# CPU3.net
KiCad netlist of a schematic drawn in Altium Designer
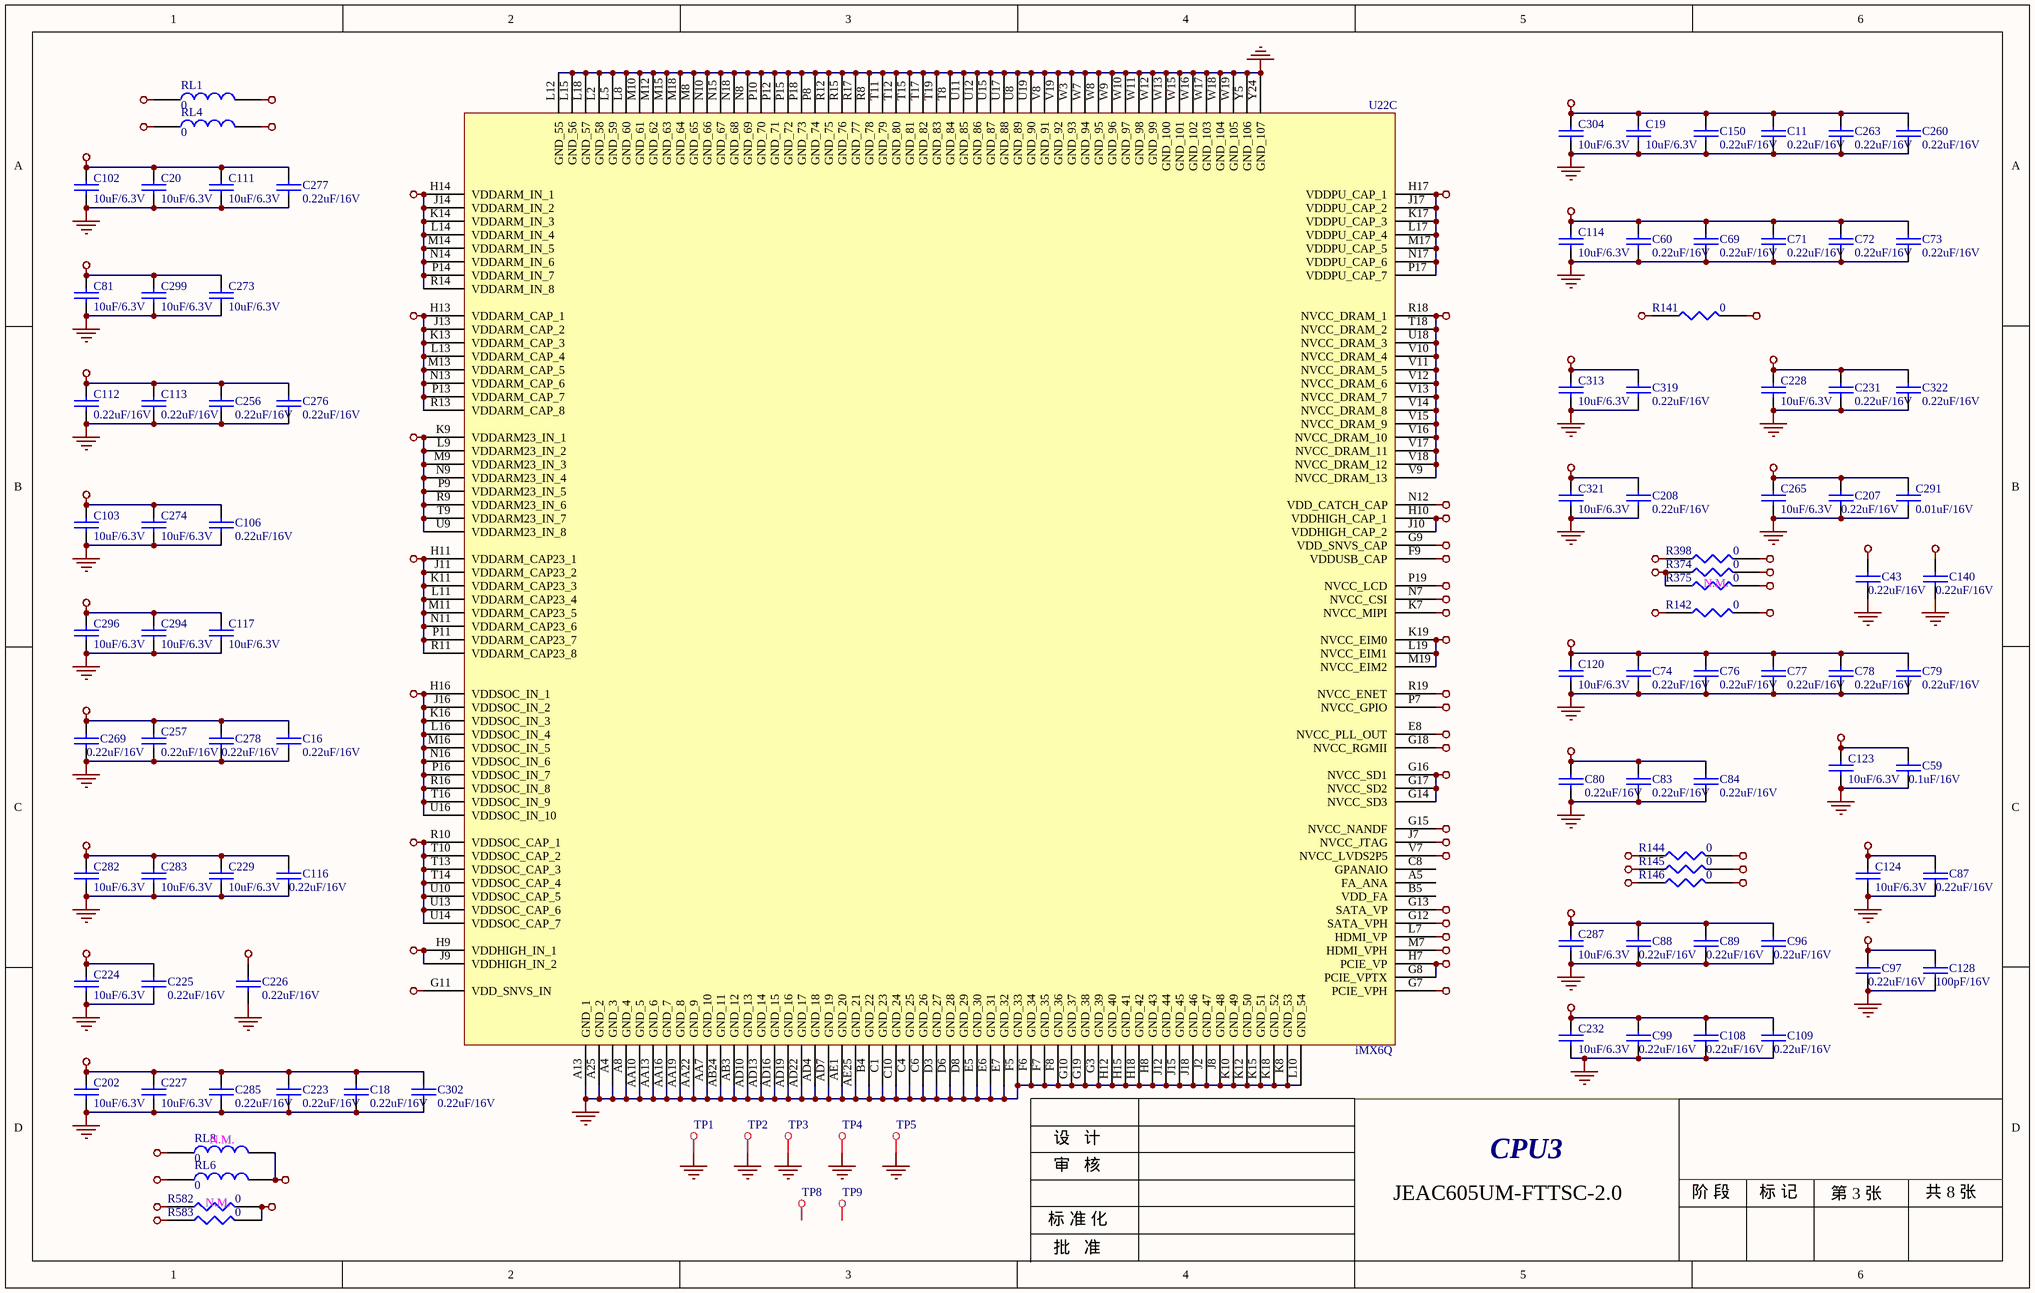
[diagram p0: CPU3.schdoc]

(export (version "E")
  (design (tool "Eeschema 10.0.6"))
  (components
    (comp (ref "C11")
      (value "0.22uF/16V")
      (footprint "C0402")
      (description "Capacitor")
      (libsource (lib "*") (part "CAP"))
    )
    (comp (ref "C16")
      (value "0.22uF/16V")
      (footprint "C0402")
      (description "Capacitor")
      (libsource (lib "*") (part "CAP"))
    )
    (comp (ref "C18")
      (value "0.22uF/16V")
      (footprint "C0402")
      (description "Capacitor")
      (libsource (lib "*") (part "CAP"))
    )
    (comp (ref "C19")
      (value "10uF/6.3V")
      (footprint "C0603")
      (description "Capacitor")
      (libsource (lib "*") (part "CAP"))
    )
    (comp (ref "C20")
      (value "10uF/6.3V")
      (footprint "C0603")
      (description "Capacitor")
      (libsource (lib "*") (part "CAP"))
    )
    (comp (ref "C43")
      (value "0.22uF/16V")
      (footprint "C0402")
      (description "Capacitor")
      (libsource (lib "*") (part "CAP"))
    )
    (comp (ref "C59")
      (value "0.1uF/16V")
      (footprint "C0402")
      (description "Capacitor")
      (libsource (lib "*") (part "CAP"))
    )
    (comp (ref "C60")
      (value "0.22uF/16V")
      (footprint "C0402")
      (description "Capacitor")
      (libsource (lib "*") (part "CAP"))
    )
    (comp (ref "C69")
      (value "0.22uF/16V")
      (footprint "C0402")
      (description "Capacitor")
      (libsource (lib "*") (part "CAP"))
    )
    (comp (ref "C71")
      (value "0.22uF/16V")
      (footprint "C0402")
      (description "Capacitor")
      (libsource (lib "*") (part "CAP"))
    )
    (comp (ref "C72")
      (value "0.22uF/16V")
      (footprint "C0402")
      (description "Capacitor")
      (libsource (lib "*") (part "CAP"))
    )
    (comp (ref "C73")
      (value "0.22uF/16V")
      (footprint "C0402")
      (description "Capacitor")
      (libsource (lib "*") (part "CAP"))
    )
    (comp (ref "C74")
      (value "0.22uF/16V")
      (footprint "C0402")
      (description "Capacitor")
      (libsource (lib "*") (part "CAP"))
    )
    (comp (ref "C76")
      (value "0.22uF/16V")
      (footprint "C0402")
      (description "Capacitor")
      (libsource (lib "*") (part "CAP"))
    )
    (comp (ref "C77")
      (value "0.22uF/16V")
      (footprint "C0402")
      (description "Capacitor")
      (libsource (lib "*") (part "CAP"))
    )
    (comp (ref "C78")
      (value "0.22uF/16V")
      (footprint "C0402")
      (description "Capacitor")
      (libsource (lib "*") (part "CAP"))
    )
    (comp (ref "C79")
      (value "0.22uF/16V")
      (footprint "C0402")
      (description "Capacitor")
      (libsource (lib "*") (part "CAP"))
    )
    (comp (ref "C80")
      (value "0.22uF/16V")
      (footprint "C0402")
      (description "Capacitor")
      (libsource (lib "*") (part "CAP"))
    )
    (comp (ref "C81")
      (value "10uF/6.3V")
      (footprint "C0603")
      (description "Capacitor")
      (libsource (lib "*") (part "CAP"))
    )
    (comp (ref "C83")
      (value "0.22uF/16V")
      (footprint "C0402")
      (description "Capacitor")
      (libsource (lib "*") (part "CAP"))
    )
    (comp (ref "C84")
      (value "0.22uF/16V")
      (footprint "C0402")
      (description "Capacitor")
      (libsource (lib "*") (part "CAP"))
    )
    (comp (ref "C87")
      (value "0.22uF/16V")
      (footprint "C0402")
      (description "Capacitor")
      (libsource (lib "*") (part "CAP"))
    )
    (comp (ref "C88")
      (value "0.22uF/16V")
      (footprint "C0402")
      (description "Capacitor")
      (libsource (lib "*") (part "CAP"))
    )
    (comp (ref "C89")
      (value "0.22uF/16V")
      (footprint "C0402")
      (description "Capacitor")
      (libsource (lib "*") (part "CAP"))
    )
    (comp (ref "C96")
      (value "0.22uF/16V")
      (footprint "C0402")
      (description "Capacitor")
      (libsource (lib "*") (part "CAP"))
    )
    (comp (ref "C97")
      (value "0.22uF/16V")
      (footprint "C0402")
      (description "Capacitor")
      (libsource (lib "*") (part "CAP"))
    )
    (comp (ref "C99")
      (value "0.22uF/16V")
      (footprint "C0402")
      (description "Capacitor")
      (libsource (lib "*") (part "CAP"))
    )
    (comp (ref "C102")
      (value "10uF/6.3V")
      (footprint "C0603")
      (description "Capacitor")
      (libsource (lib "*") (part "CAP"))
    )
    (comp (ref "C103")
      (value "10uF/6.3V")
      (footprint "C0603")
      (description "Capacitor")
      (libsource (lib "*") (part "CAP"))
    )
    (comp (ref "C106")
      (value "0.22uF/16V")
      (footprint "C0402")
      (description "Capacitor")
      (libsource (lib "*") (part "CAP"))
    )
    (comp (ref "C108")
      (value "0.22uF/16V")
      (footprint "C0402")
      (description "Capacitor")
      (libsource (lib "*") (part "CAP"))
    )
    (comp (ref "C109")
      (value "0.22uF/16V")
      (footprint "C0402")
      (description "Capacitor")
      (libsource (lib "*") (part "CAP"))
    )
    (comp (ref "C111")
      (value "10uF/6.3V")
      (footprint "C0603")
      (description "Capacitor")
      (libsource (lib "*") (part "CAP"))
    )
    (comp (ref "C112")
      (value "0.22uF/16V")
      (footprint "C0402")
      (description "Capacitor")
      (libsource (lib "*") (part "CAP"))
    )
    (comp (ref "C113")
      (value "0.22uF/16V")
      (footprint "C0402")
      (description "Capacitor")
      (libsource (lib "*") (part "CAP"))
    )
    (comp (ref "C114")
      (value "10uF/6.3V")
      (footprint "C0603")
      (description "Capacitor")
      (libsource (lib "*") (part "CAP"))
    )
    (comp (ref "C116")
      (value "0.22uF/16V")
      (footprint "C0402")
      (description "Capacitor")
      (libsource (lib "*") (part "CAP"))
    )
    (comp (ref "C117")
      (value "10uF/6.3V")
      (footprint "C0603")
      (description "Capacitor")
      (libsource (lib "*") (part "CAP"))
    )
    (comp (ref "C120")
      (value "10uF/6.3V")
      (footprint "C0603")
      (description "Capacitor")
      (libsource (lib "*") (part "CAP"))
    )
    (comp (ref "C123")
      (value "10uF/6.3V")
      (footprint "C0603")
      (description "Capacitor")
      (libsource (lib "*") (part "CAP"))
    )
    (comp (ref "C124")
      (value "10uF/6.3V")
      (footprint "C0603")
      (description "Capacitor")
      (libsource (lib "*") (part "CAP"))
    )
    (comp (ref "C128")
      (value "100pF/16V")
      (footprint "C0402")
      (description "Capacitor")
      (libsource (lib "*") (part "CAP"))
    )
    (comp (ref "C140")
      (value "0.22uF/16V")
      (footprint "C0402")
      (description "Capacitor")
      (libsource (lib "*") (part "CAP"))
    )
    (comp (ref "C150")
      (value "0.22uF/16V")
      (footprint "C0402")
      (description "Capacitor")
      (libsource (lib "*") (part "CAP"))
    )
    (comp (ref "C202")
      (value "10uF/6.3V")
      (footprint "C0603")
      (description "Capacitor")
      (libsource (lib "*") (part "CAP"))
    )
    (comp (ref "C207")
      (value "0.22uF/16V")
      (footprint "C0402")
      (description "Capacitor")
      (libsource (lib "*") (part "CAP"))
    )
    (comp (ref "C208")
      (value "0.22uF/16V")
      (footprint "C0402")
      (description "Capacitor")
      (libsource (lib "*") (part "CAP"))
    )
    (comp (ref "C223")
      (value "0.22uF/16V")
      (footprint "C0402")
      (description "Capacitor")
      (libsource (lib "*") (part "CAP"))
    )
    (comp (ref "C224")
      (value "10uF/6.3V")
      (footprint "C0603")
      (description "Capacitor")
      (libsource (lib "*") (part "CAP"))
    )
    (comp (ref "C225")
      (value "0.22uF/16V")
      (footprint "C0402")
      (description "Capacitor")
      (libsource (lib "*") (part "CAP"))
    )
    (comp (ref "C226")
      (value "0.22uF/16V")
      (footprint "C0402")
      (description "Capacitor")
      (libsource (lib "*") (part "CAP"))
    )
    (comp (ref "C227")
      (value "10uF/6.3V")
      (footprint "C0603")
      (description "Capacitor")
      (libsource (lib "*") (part "CAP"))
    )
    (comp (ref "C228")
      (value "10uF/6.3V")
      (footprint "C0603")
      (description "Capacitor")
      (libsource (lib "*") (part "CAP"))
    )
    (comp (ref "C229")
      (value "10uF/6.3V")
      (footprint "C0603")
      (description "Capacitor")
      (libsource (lib "*") (part "CAP"))
    )
    (comp (ref "C231")
      (value "0.22uF/16V")
      (footprint "C0402")
      (description "Capacitor")
      (libsource (lib "*") (part "CAP"))
    )
    (comp (ref "C232")
      (value "10uF/6.3V")
      (footprint "C0603")
      (description "Capacitor")
      (libsource (lib "*") (part "CAP"))
    )
    (comp (ref "C256")
      (value "0.22uF/16V")
      (footprint "C0402")
      (description "Capacitor")
      (libsource (lib "*") (part "CAP"))
    )
    (comp (ref "C257")
      (value "0.22uF/16V")
      (footprint "C0402")
      (description "Capacitor")
      (libsource (lib "*") (part "CAP"))
    )
    (comp (ref "C260")
      (value "0.22uF/16V")
      (footprint "C0402")
      (description "Capacitor")
      (libsource (lib "*") (part "CAP"))
    )
    (comp (ref "C263")
      (value "0.22uF/16V")
      (footprint "C0402")
      (description "Capacitor")
      (libsource (lib "*") (part "CAP"))
    )
    (comp (ref "C265")
      (value "10uF/6.3V")
      (footprint "C0603")
      (description "Capacitor")
      (libsource (lib "*") (part "CAP"))
    )
    (comp (ref "C269")
      (value "0.22uF/16V")
      (footprint "C0402")
      (description "Capacitor")
      (libsource (lib "*") (part "CAP"))
    )
    (comp (ref "C273")
      (value "10uF/6.3V")
      (footprint "C0603")
      (description "Capacitor")
      (libsource (lib "*") (part "CAP"))
    )
    (comp (ref "C274")
      (value "10uF/6.3V")
      (footprint "C0603")
      (description "Capacitor")
      (libsource (lib "*") (part "CAP"))
    )
    (comp (ref "C276")
      (value "0.22uF/16V")
      (footprint "C0402")
      (description "Capacitor")
      (libsource (lib "*") (part "CAP"))
    )
    (comp (ref "C277")
      (value "0.22uF/16V")
      (footprint "C0402")
      (description "Capacitor")
      (libsource (lib "*") (part "CAP"))
    )
    (comp (ref "C278")
      (value "0.22uF/16V")
      (footprint "C0402")
      (description "Capacitor")
      (libsource (lib "*") (part "CAP"))
    )
    (comp (ref "C282")
      (value "10uF/6.3V")
      (footprint "C0603")
      (description "Capacitor")
      (libsource (lib "*") (part "CAP"))
    )
    (comp (ref "C283")
      (value "10uF/6.3V")
      (footprint "C0603")
      (description "Capacitor")
      (libsource (lib "*") (part "CAP"))
    )
    (comp (ref "C285")
      (value "0.22uF/16V")
      (footprint "C0402")
      (description "Capacitor")
      (libsource (lib "*") (part "CAP"))
    )
    (comp (ref "C287")
      (value "10uF/6.3V")
      (footprint "C0603")
      (description "Capacitor")
      (libsource (lib "*") (part "CAP"))
    )
    (comp (ref "C291")
      (value "0.01uF/16V")
      (footprint "C0402")
      (description "Capacitor")
      (libsource (lib "*") (part "CAP"))
    )
    (comp (ref "C294")
      (value "10uF/6.3V")
      (footprint "C0603")
      (description "Capacitor")
      (libsource (lib "*") (part "CAP"))
    )
    (comp (ref "C296")
      (value "10uF/6.3V")
      (footprint "C0603")
      (description "Capacitor")
      (libsource (lib "*") (part "CAP"))
    )
    (comp (ref "C299")
      (value "10uF/6.3V")
      (footprint "C0603")
      (description "Capacitor")
      (libsource (lib "*") (part "CAP"))
    )
    (comp (ref "C302")
      (value "0.22uF/16V")
      (footprint "C0402")
      (description "Capacitor")
      (libsource (lib "*") (part "CAP"))
    )
    (comp (ref "C304")
      (value "10uF/6.3V")
      (footprint "C0603")
      (description "Capacitor")
      (libsource (lib "*") (part "CAP"))
    )
    (comp (ref "C313")
      (value "10uF/6.3V")
      (footprint "C0603")
      (description "Capacitor")
      (libsource (lib "*") (part "CAP"))
    )
    (comp (ref "C319")
      (value "0.22uF/16V")
      (footprint "C0402")
      (description "Capacitor")
      (libsource (lib "*") (part "CAP"))
    )
    (comp (ref "C321")
      (value "10uF/6.3V")
      (footprint "C0603")
      (description "Capacitor")
      (libsource (lib "*") (part "CAP"))
    )
    (comp (ref "C322")
      (value "0.22uF/16V")
      (footprint "C0402")
      (description "Capacitor")
      (libsource (lib "*") (part "CAP"))
    )
    (comp (ref "R141") (value "0") (footprint "R0402") (libsource (lib "*") (part "RES1")))
    (comp (ref "R142") (value "0") (footprint "R0402") (libsource (lib "*") (part "RES1")))
    (comp (ref "R144") (value "0") (footprint "R0402") (libsource (lib "*") (part "RES1")))
    (comp (ref "R145") (value "0") (footprint "R0402") (libsource (lib "*") (part "RES1")))
    (comp (ref "R146") (value "0") (footprint "R0402") (libsource (lib "*") (part "RES1")))
    (comp (ref "R374") (value "0") (footprint "R0402") (libsource (lib "*") (part "RES1")))
    (comp (ref "R375") (value "0") (footprint "R0402") (libsource (lib "*") (part "RES1")))
    (comp (ref "R398") (value "0") (footprint "R0402") (libsource (lib "*") (part "RES1")))
    (comp (ref "R582") (value "0") (footprint "R0402") (libsource (lib "*") (part "RES1")))
    (comp (ref "R583") (value "0") (footprint "R0402") (libsource (lib "*") (part "RES1")))
    (comp (ref "RL1") (value "0") (footprint "L0805") (libsource (lib "*") (part "INDUCTOR")))
    (comp (ref "RL4") (value "0") (footprint "L0603") (libsource (lib "*") (part "INDUCTOR")))
    (comp (ref "RL6") (value "0") (footprint "L0603") (libsource (lib "*") (part "INDUCTOR")))
    (comp (ref "RL8") (value "0") (footprint "L0603") (libsource (lib "*") (part "INDUCTOR")))
    (comp (ref "TP1")
      (value "Testpoint")
      (footprint "PC3_5D2_0")
      (libsource (lib "DXP-SCHLIB") (part "Testpoint"))
    )
    (comp (ref "TP2")
      (value "Testpoint")
      (footprint "PC3_5D2_0")
      (libsource (lib "DXP-SCHLIB") (part "Testpoint"))
    )
    (comp (ref "TP3")
      (value "Testpoint")
      (footprint "PC3_5D2_0")
      (libsource (lib "DXP-SCHLIB") (part "Testpoint"))
    )
    (comp (ref "TP4")
      (value "Testpoint")
      (footprint "PC3_5D2_0")
      (libsource (lib "DXP-SCHLIB") (part "Testpoint"))
    )
    (comp (ref "TP5")
      (value "Testpoint")
      (footprint "PC3_5D2_0")
      (libsource (lib "DXP-SCHLIB") (part "Testpoint"))
    )
    (comp (ref "TP8")
      (value "Testpoint")
      (footprint "MTH059_06")
      (libsource (lib "DXP-SCHLIB") (part "Testpoint"))
    )
    (comp (ref "TP9")
      (value "Testpoint")
      (footprint "MTH059_06")
      (libsource (lib "DXP-SCHLIB") (part "Testpoint"))
    )
    (comp (ref "U22") (value "iMX6Q") (footprint "U-BGA-624-0_8") (libsource (lib "Schlib1") (part "IMX6Q")))
  )
  (nets
    (net (code "1") (name "GND") (class "Default")
      (node (ref "C102") (pin "2") (pinfunction "2_2") (pintype "passive"))
      (node (ref "C103") (pin "2") (pinfunction "2_2") (pintype "passive"))
      (node (ref "C106") (pin "2") (pinfunction "2_2") (pintype "passive"))
      (node (ref "C108") (pin "2") (pinfunction "2_2") (pintype "passive"))
      (node (ref "C109") (pin "2") (pinfunction "2_2") (pintype "passive"))
      (node (ref "C11") (pin "2") (pinfunction "2_2") (pintype "passive"))
      (node (ref "C111") (pin "2") (pinfunction "2_2") (pintype "passive"))
      (node (ref "C112") (pin "2") (pinfunction "2_2") (pintype "passive"))
      (node (ref "C113") (pin "2") (pinfunction "2_2") (pintype "passive"))
      (node (ref "C114") (pin "2") (pinfunction "2_2") (pintype "passive"))
      (node (ref "C116") (pin "2") (pinfunction "2_2") (pintype "passive"))
      (node (ref "C117") (pin "2") (pinfunction "2_2") (pintype "passive"))
      (node (ref "C120") (pin "2") (pinfunction "2_2") (pintype "passive"))
      (node (ref "C123") (pin "2") (pinfunction "2_2") (pintype "passive"))
      (node (ref "C124") (pin "2") (pinfunction "2_2") (pintype "passive"))
      (node (ref "C128") (pin "2") (pinfunction "2_2") (pintype "passive"))
      (node (ref "C140") (pin "2") (pinfunction "2_2") (pintype "passive"))
      (node (ref "C150") (pin "2") (pinfunction "2_2") (pintype "passive"))
      (node (ref "C16") (pin "2") (pinfunction "2_2") (pintype "passive"))
      (node (ref "C18") (pin "2") (pinfunction "2_2") (pintype "passive"))
      (node (ref "C19") (pin "2") (pinfunction "2_2") (pintype "passive"))
      (node (ref "C20") (pin "2") (pinfunction "2_2") (pintype "passive"))
      (node (ref "C202") (pin "2") (pinfunction "2_2") (pintype "passive"))
      (node (ref "C207") (pin "2") (pinfunction "2_2") (pintype "passive"))
      (node (ref "C208") (pin "2") (pinfunction "2_2") (pintype "passive"))
      (node (ref "C223") (pin "2") (pinfunction "2_2") (pintype "passive"))
      (node (ref "C224") (pin "2") (pinfunction "2_2") (pintype "passive"))
      (node (ref "C225") (pin "2") (pinfunction "2_2") (pintype "passive"))
      (node (ref "C226") (pin "2") (pinfunction "2_2") (pintype "passive"))
      (node (ref "C227") (pin "2") (pinfunction "2_2") (pintype "passive"))
      (node (ref "C228") (pin "2") (pinfunction "2_2") (pintype "passive"))
      (node (ref "C229") (pin "2") (pinfunction "2_2") (pintype "passive"))
      (node (ref "C231") (pin "2") (pinfunction "2_2") (pintype "passive"))
      (node (ref "C232") (pin "2") (pinfunction "2_2") (pintype "passive"))
      (node (ref "C256") (pin "2") (pinfunction "2_2") (pintype "passive"))
      (node (ref "C257") (pin "2") (pinfunction "2_2") (pintype "passive"))
      (node (ref "C260") (pin "2") (pinfunction "2_2") (pintype "passive"))
      (node (ref "C263") (pin "2") (pinfunction "2_2") (pintype "passive"))
      (node (ref "C265") (pin "2") (pinfunction "2_2") (pintype "passive"))
      (node (ref "C269") (pin "2") (pinfunction "2_2") (pintype "passive"))
      (node (ref "C273") (pin "2") (pinfunction "2_2") (pintype "passive"))
      (node (ref "C274") (pin "2") (pinfunction "2_2") (pintype "passive"))
      (node (ref "C276") (pin "2") (pinfunction "2_2") (pintype "passive"))
      (node (ref "C277") (pin "2") (pinfunction "2_2") (pintype "passive"))
      (node (ref "C278") (pin "2") (pinfunction "2_2") (pintype "passive"))
      (node (ref "C282") (pin "2") (pinfunction "2_2") (pintype "passive"))
      (node (ref "C283") (pin "2") (pinfunction "2_2") (pintype "passive"))
      (node (ref "C285") (pin "2") (pinfunction "2_2") (pintype "passive"))
      (node (ref "C287") (pin "2") (pinfunction "2_2") (pintype "passive"))
      (node (ref "C291") (pin "2") (pinfunction "2_2") (pintype "passive"))
      (node (ref "C294") (pin "2") (pinfunction "2_2") (pintype "passive"))
      (node (ref "C296") (pin "2") (pinfunction "2_2") (pintype "passive"))
      (node (ref "C299") (pin "2") (pinfunction "2_2") (pintype "passive"))
      (node (ref "C302") (pin "2") (pinfunction "2_2") (pintype "passive"))
      (node (ref "C304") (pin "2") (pinfunction "2_2") (pintype "passive"))
      (node (ref "C313") (pin "2") (pinfunction "2_2") (pintype "passive"))
      (node (ref "C319") (pin "2") (pinfunction "2_2") (pintype "passive"))
      (node (ref "C321") (pin "2") (pinfunction "2_2") (pintype "passive"))
      (node (ref "C322") (pin "2") (pinfunction "2_2") (pintype "passive"))
      (node (ref "C43") (pin "2") (pinfunction "2_2") (pintype "passive"))
      (node (ref "C59") (pin "2") (pinfunction "2_2") (pintype "passive"))
      (node (ref "C60") (pin "2") (pinfunction "2_2") (pintype "passive"))
      (node (ref "C69") (pin "2") (pinfunction "2_2") (pintype "passive"))
      (node (ref "C71") (pin "2") (pinfunction "2_2") (pintype "passive"))
      (node (ref "C72") (pin "2") (pinfunction "2_2") (pintype "passive"))
      (node (ref "C73") (pin "2") (pinfunction "2_2") (pintype "passive"))
      (node (ref "C74") (pin "2") (pinfunction "2_2") (pintype "passive"))
      (node (ref "C76") (pin "2") (pinfunction "2_2") (pintype "passive"))
      (node (ref "C77") (pin "2") (pinfunction "2_2") (pintype "passive"))
      (node (ref "C78") (pin "2") (pinfunction "2_2") (pintype "passive"))
      (node (ref "C79") (pin "2") (pinfunction "2_2") (pintype "passive"))
      (node (ref "C80") (pin "2") (pinfunction "2_2") (pintype "passive"))
      (node (ref "C81") (pin "2") (pinfunction "2_2") (pintype "passive"))
      (node (ref "C83") (pin "2") (pinfunction "2_2") (pintype "passive"))
      (node (ref "C84") (pin "2") (pinfunction "2_2") (pintype "passive"))
      (node (ref "C87") (pin "2") (pinfunction "2_2") (pintype "passive"))
      (node (ref "C88") (pin "2") (pinfunction "2_2") (pintype "passive"))
      (node (ref "C89") (pin "2") (pinfunction "2_2") (pintype "passive"))
      (node (ref "C96") (pin "2") (pinfunction "2_2") (pintype "passive"))
      (node (ref "C97") (pin "2") (pinfunction "2_2") (pintype "passive"))
      (node (ref "C99") (pin "2") (pinfunction "2_2") (pintype "passive"))
      (node (ref "TP1") (pin "1") (pinfunction "TP_1") (pintype "passive"))
      (node (ref "TP2") (pin "1") (pinfunction "TP_1") (pintype "passive"))
      (node (ref "TP3") (pin "1") (pinfunction "TP_1") (pintype "passive"))
      (node (ref "TP4") (pin "1") (pinfunction "TP_1") (pintype "passive"))
      (node (ref "TP5") (pin "1") (pinfunction "TP_1") (pintype "passive"))
      (node (ref "U22") (pin "A13") (pinfunction "GND_1_A13") (pintype "passive"))
      (node (ref "U22") (pin "A25") (pinfunction "GND_2_A25") (pintype "passive"))
      (node (ref "U22") (pin "A4") (pinfunction "GND_3_A4") (pintype "passive"))
      (node (ref "U22") (pin "A8") (pinfunction "GND_4_A8") (pintype "passive"))
      (node (ref "U22") (pin "AA10") (pinfunction "GND_5_AA10") (pintype "passive"))
      (node (ref "U22") (pin "AA13") (pinfunction "GND_6_AA13") (pintype "passive"))
      (node (ref "U22") (pin "AA16") (pinfunction "GND_7_AA16") (pintype "passive"))
      (node (ref "U22") (pin "AA19") (pinfunction "GND_8_AA19") (pintype "passive"))
      (node (ref "U22") (pin "AA22") (pinfunction "GND_9_AA22") (pintype "passive"))
      (node (ref "U22") (pin "AA7") (pinfunction "GND_10_AA7") (pintype "passive"))
      (node (ref "U22") (pin "AB24") (pinfunction "GND_11_AB24") (pintype "passive"))
      (node (ref "U22") (pin "AB3") (pinfunction "GND_12_AB3") (pintype "passive"))
      (node (ref "U22") (pin "AD10") (pinfunction "GND_13_AD10") (pintype "passive"))
      (node (ref "U22") (pin "AD13") (pinfunction "GND_14_AD13") (pintype "passive"))
      (node (ref "U22") (pin "AD16") (pinfunction "GND_15_AD16") (pintype "passive"))
      (node (ref "U22") (pin "AD19") (pinfunction "GND_16_AD19") (pintype "passive"))
      (node (ref "U22") (pin "AD22") (pinfunction "GND_17_AD22") (pintype "passive"))
      (node (ref "U22") (pin "AD4") (pinfunction "GND_18_AD4") (pintype "passive"))
      (node (ref "U22") (pin "AD7") (pinfunction "GND_19_AD7") (pintype "passive"))
      (node (ref "U22") (pin "AE1") (pinfunction "GND_20_AE1") (pintype "passive"))
      (node (ref "U22") (pin "AE25") (pinfunction "GND_21_AE25") (pintype "passive"))
      (node (ref "U22") (pin "B4") (pinfunction "GND_22_B4") (pintype "passive"))
      (node (ref "U22") (pin "C1") (pinfunction "GND_23_C1") (pintype "passive"))
      (node (ref "U22") (pin "C10") (pinfunction "GND_24_C10") (pintype "passive"))
      (node (ref "U22") (pin "C4") (pinfunction "GND_25_C4") (pintype "passive"))
      (node (ref "U22") (pin "C6") (pinfunction "GND_26_C6") (pintype "passive"))
      (node (ref "U22") (pin "D3") (pinfunction "GND_27_D3") (pintype "passive"))
      (node (ref "U22") (pin "D6") (pinfunction "GND_28_D6") (pintype "passive"))
      (node (ref "U22") (pin "D8") (pinfunction "GND_29_D8") (pintype "passive"))
      (node (ref "U22") (pin "E5") (pinfunction "GND_30_E5") (pintype "passive"))
      (node (ref "U22") (pin "E6") (pinfunction "GND_31_E6") (pintype "passive"))
      (node (ref "U22") (pin "E7") (pinfunction "GND_32_E7") (pintype "passive"))
      (node (ref "U22") (pin "F5") (pinfunction "GND_33_F5") (pintype "passive"))
      (node (ref "U22") (pin "F6") (pinfunction "GND_34_F6") (pintype "passive"))
      (node (ref "U22") (pin "F7") (pinfunction "GND_35_F7") (pintype "passive"))
      (node (ref "U22") (pin "F8") (pinfunction "GND_36_F8") (pintype "passive"))
      (node (ref "U22") (pin "G10") (pinfunction "GND_37_G10") (pintype "passive"))
      (node (ref "U22") (pin "G19") (pinfunction "GND_38_G19") (pintype "passive"))
      (node (ref "U22") (pin "G3") (pinfunction "GND_39_G3") (pintype "passive"))
      (node (ref "U22") (pin "H12") (pinfunction "GND_40_H12") (pintype "passive"))
      (node (ref "U22") (pin "H15") (pinfunction "GND_41_H15") (pintype "passive"))
      (node (ref "U22") (pin "H18") (pinfunction "GND_42_H18") (pintype "passive"))
      (node (ref "U22") (pin "H8") (pinfunction "GND_43_H8") (pintype "passive"))
      (node (ref "U22") (pin "J12") (pinfunction "GND_44_J12") (pintype "passive"))
      (node (ref "U22") (pin "J15") (pinfunction "GND_45_J15") (pintype "passive"))
      (node (ref "U22") (pin "J18") (pinfunction "GND_46_J18") (pintype "passive"))
      (node (ref "U22") (pin "J2") (pinfunction "GND_47_J2") (pintype "passive"))
      (node (ref "U22") (pin "J8") (pinfunction "GND_48_J8") (pintype "passive"))
      (node (ref "U22") (pin "K10") (pinfunction "GND_49_K10") (pintype "passive"))
      (node (ref "U22") (pin "K12") (pinfunction "GND_50_K12") (pintype "passive"))
      (node (ref "U22") (pin "K15") (pinfunction "GND_51_K15") (pintype "passive"))
      (node (ref "U22") (pin "K18") (pinfunction "GND_52_K18") (pintype "passive"))
      (node (ref "U22") (pin "K8") (pinfunction "GND_53_K8") (pintype "passive"))
      (node (ref "U22") (pin "L10") (pinfunction "GND_54_L10") (pintype "passive"))
      (node (ref "U22") (pin "L12") (pinfunction "GND_55_L12") (pintype "passive"))
      (node (ref "U22") (pin "L15") (pinfunction "GND_56_L15") (pintype "passive"))
      (node (ref "U22") (pin "L18") (pinfunction "GND_57_L18") (pintype "passive"))
      (node (ref "U22") (pin "L2") (pinfunction "GND_58_L2") (pintype "passive"))
      (node (ref "U22") (pin "L5") (pinfunction "GND_59_L5") (pintype "passive"))
      (node (ref "U22") (pin "L8") (pinfunction "GND_60_L8") (pintype "passive"))
      (node (ref "U22") (pin "M10") (pinfunction "GND_61_M10") (pintype "passive"))
      (node (ref "U22") (pin "M12") (pinfunction "GND_62_M12") (pintype "passive"))
      (node (ref "U22") (pin "M15") (pinfunction "GND_63_M15") (pintype "passive"))
      (node (ref "U22") (pin "M18") (pinfunction "GND_64_M18") (pintype "passive"))
      (node (ref "U22") (pin "M8") (pinfunction "GND_65_M8") (pintype "passive"))
      (node (ref "U22") (pin "N10") (pinfunction "GND_66_N10") (pintype "passive"))
      (node (ref "U22") (pin "N15") (pinfunction "GND_67_N15") (pintype "passive"))
      (node (ref "U22") (pin "N18") (pinfunction "GND_68_N18") (pintype "passive"))
      (node (ref "U22") (pin "N8") (pinfunction "GND_69_N8") (pintype "passive"))
      (node (ref "U22") (pin "P10") (pinfunction "GND_70_P10") (pintype "passive"))
      (node (ref "U22") (pin "P12") (pinfunction "GND_71_P12") (pintype "passive"))
      (node (ref "U22") (pin "P15") (pinfunction "GND_72_P15") (pintype "passive"))
      (node (ref "U22") (pin "P18") (pinfunction "GND_73_P18") (pintype "passive"))
      (node (ref "U22") (pin "P8") (pinfunction "GND_74_P8") (pintype "passive"))
      (node (ref "U22") (pin "R12") (pinfunction "GND_75_R12") (pintype "passive"))
      (node (ref "U22") (pin "R15") (pinfunction "GND_76_R15") (pintype "passive"))
      (node (ref "U22") (pin "R17") (pinfunction "GND_77_R17") (pintype "passive"))
      (node (ref "U22") (pin "R8") (pinfunction "GND_78_R8") (pintype "passive"))
      (node (ref "U22") (pin "T11") (pinfunction "GND_79_T11") (pintype "passive"))
      (node (ref "U22") (pin "T12") (pinfunction "GND_80_T12") (pintype "passive"))
      (node (ref "U22") (pin "T15") (pinfunction "GND_81_T15") (pintype "passive"))
      (node (ref "U22") (pin "T17") (pinfunction "GND_82_T17") (pintype "passive"))
      (node (ref "U22") (pin "T19") (pinfunction "GND_83_T19") (pintype "passive"))
      (node (ref "U22") (pin "T8") (pinfunction "GND_84_T8") (pintype "passive"))
      (node (ref "U22") (pin "U11") (pinfunction "GND_85_U11") (pintype "passive"))
      (node (ref "U22") (pin "U12") (pinfunction "GND_86_U12") (pintype "passive"))
      (node (ref "U22") (pin "U15") (pinfunction "GND_87_U15") (pintype "passive"))
      (node (ref "U22") (pin "U17") (pinfunction "GND_88_U17") (pintype "passive"))
      (node (ref "U22") (pin "U19") (pinfunction "GND_90_U19") (pintype "passive"))
      (node (ref "U22") (pin "U8") (pinfunction "GND_89_U8") (pintype "passive"))
      (node (ref "U22") (pin "V19") (pinfunction "GND_92_V19") (pintype "passive"))
      (node (ref "U22") (pin "V8") (pinfunction "GND_91_V8") (pintype "passive"))
      (node (ref "U22") (pin "W10") (pinfunction "GND_97_W10") (pintype "passive"))
      (node (ref "U22") (pin "W11") (pinfunction "GND_98_W11") (pintype "passive"))
      (node (ref "U22") (pin "W12") (pinfunction "GND_99_W12") (pintype "passive"))
      (node (ref "U22") (pin "W13") (pinfunction "GND_100_W13") (pintype "passive"))
      (node (ref "U22") (pin "W15") (pinfunction "GND_101_W15") (pintype "passive"))
      (node (ref "U22") (pin "W16") (pinfunction "GND_102_W16") (pintype "passive"))
      (node (ref "U22") (pin "W17") (pinfunction "GND_103_W17") (pintype "passive"))
      (node (ref "U22") (pin "W18") (pinfunction "GND_104_W18") (pintype "passive"))
      (node (ref "U22") (pin "W19") (pinfunction "GND_105_W19") (pintype "passive"))
      (node (ref "U22") (pin "W3") (pinfunction "GND_93_W3") (pintype "passive"))
      (node (ref "U22") (pin "W7") (pinfunction "GND_94_W7") (pintype "passive"))
      (node (ref "U22") (pin "W8") (pinfunction "GND_95_W8") (pintype "passive"))
      (node (ref "U22") (pin "W9") (pinfunction "GND_96_W9") (pintype "passive"))
      (node (ref "U22") (pin "Y24") (pinfunction "GND_107_Y24") (pintype "passive"))
      (node (ref "U22") (pin "Y5") (pinfunction "GND_106_Y5") (pintype "passive"))
    )
    (net (code "2") (name "NVCC_PLL_OUT") (class "Default")
      (node (ref "C207") (pin "1") (pinfunction "1_1") (pintype "passive"))
      (node (ref "C265") (pin "1") (pinfunction "1_1") (pintype "passive"))
      (node (ref "C291") (pin "1") (pinfunction "1_1") (pintype "passive"))
      (node (ref "R142") (pin "1") (pinfunction "1_1") (pintype "passive"))
      (node (ref "U22") (pin "E8") (pinfunction "NVCC_PLL_OUT_E8") (pintype "passive"))
    )
    (net (code "3") (name "VCC_1V1") (class "Default")
      (node (ref "R142") (pin "2") (pinfunction "2_2") (pintype "passive"))
    )
    (net (code "4") (name "VCC_1V5") (class "Default")
      (node (ref "C124") (pin "1") (pinfunction "1_1") (pintype "passive"))
      (node (ref "C87") (pin "1") (pinfunction "1_1") (pintype "passive"))
      (node (ref "U22") (pin "G18") (pinfunction "NVCC_RGMII_G18") (pintype "passive"))
    )
    (net (code "5") (name "VCC_2V8") (class "Default")
      (node (ref "R398") (pin "2") (pinfunction "2_2") (pintype "passive"))
    )
    (net (code "6") (name "VCC_3V") (class "Default")
      (node (ref "C120") (pin "1") (pinfunction "1_1") (pintype "passive"))
      (node (ref "C74") (pin "1") (pinfunction "1_1") (pintype "passive"))
      (node (ref "C76") (pin "1") (pinfunction "1_1") (pintype "passive"))
      (node (ref "C77") (pin "1") (pinfunction "1_1") (pintype "passive"))
      (node (ref "C78") (pin "1") (pinfunction "1_1") (pintype "passive"))
      (node (ref "C79") (pin "1") (pinfunction "1_1") (pintype "passive"))
      (node (ref "C80") (pin "1") (pinfunction "1_1") (pintype "passive"))
      (node (ref "C83") (pin "1") (pinfunction "1_1") (pintype "passive"))
      (node (ref "C84") (pin "1") (pinfunction "1_1") (pintype "passive"))
      (node (ref "RL8") (pin "1") (pinfunction "1_1") (pintype "passive"))
      (node (ref "U22") (pin "G14") (pinfunction "NVCC_SD3_G14") (pintype "passive"))
      (node (ref "U22") (pin "G15") (pinfunction "NVCC_NANDF_G15") (pintype "passive"))
      (node (ref "U22") (pin "G16") (pinfunction "NVCC_SD1_G16") (pintype "passive"))
      (node (ref "U22") (pin "G17") (pinfunction "NVCC_SD2_G17") (pintype "passive"))
      (node (ref "U22") (pin "J7") (pinfunction "NVCC_JTAG_J7") (pintype "passive"))
      (node (ref "U22") (pin "K19") (pinfunction "NVCC_EIM0_K19") (pintype "passive"))
      (node (ref "U22") (pin "L19") (pinfunction "NVCC_EIM1_L19") (pintype "passive"))
      (node (ref "U22") (pin "M19") (pinfunction "NVCC_EIM2_M19") (pintype "passive"))
      (node (ref "U22") (pin "P19") (pinfunction "NVCC_LCD_P19") (pintype "passive"))
      (node (ref "U22") (pin "P7") (pinfunction "NVCC_GPIO_P7") (pintype "passive"))
      (node (ref "U22") (pin "R19") (pinfunction "NVCC_ENET_R19") (pintype "passive"))
    )
    (net (code "7") (name "VCC_3V1") (class "Default")
      (node (ref "R582") (pin "1") (pinfunction "1_1") (pintype "passive"))
      (node (ref "RL6") (pin "1") (pinfunction "1_1") (pintype "passive"))
    )
    (net (code "8") (name "VCC_CSI") (class "Default")
      (node (ref "C43") (pin "1") (pinfunction "1_1") (pintype "passive"))
      (node (ref "R398") (pin "1") (pinfunction "1_1") (pintype "passive"))
      (node (ref "U22") (pin "N7") (pinfunction "NVCC_CSI_N7") (pintype "passive"))
    )
    (net (code "9") (name "VCC_MIPI") (class "Default")
      (node (ref "C140") (pin "1") (pinfunction "1_1") (pintype "passive"))
      (node (ref "R374") (pin "1") (pinfunction "1_1") (pintype "passive"))
      (node (ref "R375") (pin "1") (pinfunction "1_1") (pintype "passive"))
      (node (ref "U22") (pin "K7") (pinfunction "NVCC_MIPI_K7") (pintype "passive"))
    )
    (net (code "10") (name "VCC_MIPIB") (class "Default")
      (node (ref "R375") (pin "2") (pinfunction "2_2") (pintype "passive"))
    )
    (net (code "11") (name "VDDHIGH_IN") (class "Default")
      (node (ref "C224") (pin "1") (pinfunction "1_1") (pintype "passive"))
      (node (ref "C225") (pin "1") (pinfunction "1_1") (pintype "passive"))
      (node (ref "RL6") (pin "2") (pinfunction "2_2") (pintype "passive"))
      (node (ref "RL8") (pin "2") (pinfunction "2_2") (pintype "passive"))
      (node (ref "U22") (pin "H9") (pinfunction "VDDHIGH_IN_1_H9") (pintype "passive"))
      (node (ref "U22") (pin "J9") (pinfunction "VDDHIGH_IN_2_J9") (pintype "passive"))
    )
    (net (code "12") (name "VDDUSB_CAP") (class "Default")
      (node (ref "C123") (pin "1") (pinfunction "1_1") (pintype "passive"))
      (node (ref "C59") (pin "1") (pinfunction "1_1") (pintype "passive"))
      (node (ref "U22") (pin "F9") (pinfunction "VDDUSB_CAP_F9") (pintype "passive"))
    )
    (net (code "13") (name "VDD_ARM23_IN") (class "Default")
      (node (ref "C103") (pin "1") (pinfunction "1_1") (pintype "passive"))
      (node (ref "C106") (pin "1") (pinfunction "1_1") (pintype "passive"))
      (node (ref "C274") (pin "1") (pinfunction "1_1") (pintype "passive"))
      (node (ref "RL1") (pin "2") (pinfunction "2_2") (pintype "passive"))
      (node (ref "U22") (pin "K9") (pinfunction "VDDARM23_IN_1_K9") (pintype "passive"))
      (node (ref "U22") (pin "L9") (pinfunction "VDDARM23_IN_2_L9") (pintype "passive"))
      (node (ref "U22") (pin "M9") (pinfunction "VDDARM23_IN_3_M9") (pintype "passive"))
      (node (ref "U22") (pin "N9") (pinfunction "VDDARM23_IN_4_N9") (pintype "passive"))
      (node (ref "U22") (pin "P9") (pinfunction "VDDARM23_IN_5_P9") (pintype "passive"))
      (node (ref "U22") (pin "R9") (pinfunction "VDDARM23_IN_6_R9") (pintype "passive"))
      (node (ref "U22") (pin "T9") (pinfunction "VDDARM23_IN_7_T9") (pintype "passive"))
      (node (ref "U22") (pin "U9") (pinfunction "VDDARM23_IN_8_U9") (pintype "passive"))
    )
    (net (code "14") (name "VDD_ARM_CAP") (class "Default")
      (node (ref "C112") (pin "1") (pinfunction "1_1") (pintype "passive"))
      (node (ref "C113") (pin "1") (pinfunction "1_1") (pintype "passive"))
      (node (ref "C256") (pin "1") (pinfunction "1_1") (pintype "passive"))
      (node (ref "C273") (pin "1") (pinfunction "1_1") (pintype "passive"))
      (node (ref "C276") (pin "1") (pinfunction "1_1") (pintype "passive"))
      (node (ref "C299") (pin "1") (pinfunction "1_1") (pintype "passive"))
      (node (ref "C81") (pin "1") (pinfunction "1_1") (pintype "passive"))
      (node (ref "RL4") (pin "1") (pinfunction "1_1") (pintype "passive"))
      (node (ref "U22") (pin "H13") (pinfunction "VDDARM_CAP_1_H13") (pintype "passive"))
      (node (ref "U22") (pin "J13") (pinfunction "VDDARM_CAP_2_J13") (pintype "passive"))
      (node (ref "U22") (pin "K13") (pinfunction "VDDARM_CAP_3_K13") (pintype "passive"))
      (node (ref "U22") (pin "L13") (pinfunction "VDDARM_CAP_4_L13") (pintype "passive"))
      (node (ref "U22") (pin "M13") (pinfunction "VDDARM_CAP_5_M13") (pintype "passive"))
      (node (ref "U22") (pin "N13") (pinfunction "VDDARM_CAP_6_N13") (pintype "passive"))
      (node (ref "U22") (pin "P13") (pinfunction "VDDARM_CAP_7_P13") (pintype "passive"))
      (node (ref "U22") (pin "R13") (pinfunction "VDDARM_CAP_8_R13") (pintype "passive"))
    )
    (net (code "15") (name "VDD_ARM_CAP23") (class "Default")
      (node (ref "C117") (pin "1") (pinfunction "1_1") (pintype "passive"))
      (node (ref "C16") (pin "1") (pinfunction "1_1") (pintype "passive"))
      (node (ref "C257") (pin "1") (pinfunction "1_1") (pintype "passive"))
      (node (ref "C269") (pin "1") (pinfunction "1_1") (pintype "passive"))
      (node (ref "C278") (pin "1") (pinfunction "1_1") (pintype "passive"))
      (node (ref "C294") (pin "1") (pinfunction "1_1") (pintype "passive"))
      (node (ref "C296") (pin "1") (pinfunction "1_1") (pintype "passive"))
      (node (ref "RL4") (pin "2") (pinfunction "2_2") (pintype "passive"))
      (node (ref "U22") (pin "H11") (pinfunction "VDDARM_CAP23_1_H11") (pintype "passive"))
      (node (ref "U22") (pin "J11") (pinfunction "VDDARM_CAP23_2_J11") (pintype "passive"))
      (node (ref "U22") (pin "K11") (pinfunction "VDDARM_CAP23_3_K11") (pintype "passive"))
      (node (ref "U22") (pin "L11") (pinfunction "VDDARM_CAP23_4_L11") (pintype "passive"))
      (node (ref "U22") (pin "M11") (pinfunction "VDDARM_CAP23_5_M11") (pintype "passive"))
      (node (ref "U22") (pin "N11") (pinfunction "VDDARM_CAP23_6_N11") (pintype "passive"))
      (node (ref "U22") (pin "P11") (pinfunction "VDDARM_CAP23_7_P11") (pintype "passive"))
      (node (ref "U22") (pin "R11") (pinfunction "VDDARM_CAP23_8_R11") (pintype "passive"))
    )
    (net (code "16") (name "VDD_ARM_IN") (class "Default")
      (node (ref "C102") (pin "1") (pinfunction "1_1") (pintype "passive"))
      (node (ref "C111") (pin "1") (pinfunction "1_1") (pintype "passive"))
      (node (ref "C20") (pin "1") (pinfunction "1_1") (pintype "passive"))
      (node (ref "C277") (pin "1") (pinfunction "1_1") (pintype "passive"))
      (node (ref "RL1") (pin "1") (pinfunction "1_1") (pintype "passive"))
      (node (ref "U22") (pin "H14") (pinfunction "VDDARM_IN_1_H14") (pintype "passive"))
      (node (ref "U22") (pin "J14") (pinfunction "VDDARM_IN_2_J14") (pintype "passive"))
      (node (ref "U22") (pin "K14") (pinfunction "VDDARM_IN_3_K14") (pintype "passive"))
      (node (ref "U22") (pin "L14") (pinfunction "VDDARM_IN_4_L14") (pintype "passive"))
      (node (ref "U22") (pin "M14") (pinfunction "VDDARM_IN_5_M14") (pintype "passive"))
      (node (ref "U22") (pin "N14") (pinfunction "VDDARM_IN_6_N14") (pintype "passive"))
      (node (ref "U22") (pin "P14") (pinfunction "VDDARM_IN_7_P14") (pintype "passive"))
      (node (ref "U22") (pin "R14") (pinfunction "VDDARM_IN_8_R14") (pintype "passive"))
    )
    (net (code "17") (name "VDD_CACHE") (class "Default")
      (node (ref "C313") (pin "1") (pinfunction "1_1") (pintype "passive"))
      (node (ref "C319") (pin "1") (pinfunction "1_1") (pintype "passive"))
      (node (ref "R141") (pin "1") (pinfunction "1_1") (pintype "passive"))
      (node (ref "U22") (pin "N12") (pinfunction "VDD_CATCH_CAP_N12") (pintype "passive"))
    )
    (net (code "18") (name "VDD_DRAM_1.2V") (class "Default")
      (node (ref "C114") (pin "1") (pinfunction "1_1") (pintype "passive"))
      (node (ref "C60") (pin "1") (pinfunction "1_1") (pintype "passive"))
      (node (ref "C69") (pin "1") (pinfunction "1_1") (pintype "passive"))
      (node (ref "C71") (pin "1") (pinfunction "1_1") (pintype "passive"))
      (node (ref "C72") (pin "1") (pinfunction "1_1") (pintype "passive"))
      (node (ref "C73") (pin "1") (pinfunction "1_1") (pintype "passive"))
      (node (ref "U22") (pin "R18") (pinfunction "NVCC_DRAM_1_R18") (pintype "passive"))
      (node (ref "U22") (pin "T18") (pinfunction "NVCC_DRAM_2_T18") (pintype "passive"))
      (node (ref "U22") (pin "U18") (pinfunction "NVCC_DRAM_3_U18") (pintype "passive"))
      (node (ref "U22") (pin "V10") (pinfunction "NVCC_DRAM_4_V10") (pintype "passive"))
      (node (ref "U22") (pin "V11") (pinfunction "NVCC_DRAM_5_V11") (pintype "passive"))
      (node (ref "U22") (pin "V12") (pinfunction "NVCC_DRAM_6_V12") (pintype "passive"))
      (node (ref "U22") (pin "V13") (pinfunction "NVCC_DRAM_7_V13") (pintype "passive"))
      (node (ref "U22") (pin "V14") (pinfunction "NVCC_DRAM_8_V14") (pintype "passive"))
      (node (ref "U22") (pin "V15") (pinfunction "NVCC_DRAM_9_V15") (pintype "passive"))
      (node (ref "U22") (pin "V16") (pinfunction "NVCC_DRAM_10_V16") (pintype "passive"))
      (node (ref "U22") (pin "V17") (pinfunction "NVCC_DRAM_11_V17") (pintype "passive"))
      (node (ref "U22") (pin "V18") (pinfunction "NVCC_DRAM_12_V18") (pintype "passive"))
      (node (ref "U22") (pin "V9") (pinfunction "NVCC_DRAM_13_V9") (pintype "passive"))
    )
    (net (code "19") (name "VDD_HIGH") (class "Default")
      (node (ref "C228") (pin "1") (pinfunction "1_1") (pintype "passive"))
      (node (ref "C231") (pin "1") (pinfunction "1_1") (pintype "passive"))
      (node (ref "C322") (pin "1") (pinfunction "1_1") (pintype "passive"))
      (node (ref "R144") (pin "2") (pinfunction "2_2") (pintype "passive"))
      (node (ref "R146") (pin "2") (pinfunction "2_2") (pintype "passive"))
      (node (ref "R374") (pin "2") (pinfunction "2_2") (pintype "passive"))
      (node (ref "U22") (pin "H10") (pinfunction "VDDHIGH_CAP_1_H10") (pintype "passive"))
      (node (ref "U22") (pin "J10") (pinfunction "VDDHIGH_CAP_2_J10") (pintype "passive"))
    )
    (net (code "20") (name "VDD_LVDS2P5") (class "Default")
      (node (ref "C128") (pin "1") (pinfunction "1_1") (pintype "passive"))
      (node (ref "C97") (pin "1") (pinfunction "1_1") (pintype "passive"))
      (node (ref "R146") (pin "1") (pinfunction "1_1") (pintype "passive"))
      (node (ref "U22") (pin "V7") (pinfunction "NVCC_LVDS2P5_V7") (pintype "passive"))
    )
    (net (code "21") (name "VDD_SNVS") (class "Default")
      (node (ref "C208") (pin "1") (pinfunction "1_1") (pintype "passive"))
      (node (ref "C321") (pin "1") (pinfunction "1_1") (pintype "passive"))
      (node (ref "U22") (pin "G9") (pinfunction "VDD_SNVS_CAP_G9") (pintype "passive"))
    )
    (net (code "22") (name "VDD_SNVS_IN") (class "Default")
      (node (ref "C226") (pin "1") (pinfunction "1_1") (pintype "passive"))
      (node (ref "R582") (pin "2") (pinfunction "2_2") (pintype "passive"))
      (node (ref "R583") (pin "2") (pinfunction "2_2") (pintype "passive"))
      (node (ref "U22") (pin "G11") (pinfunction "VDD_SNVS_IN_G11") (pintype "passive"))
    )
    (net (code "23") (name "VDD_SOC") (class "Default")
      (node (ref "C18") (pin "1") (pinfunction "1_1") (pintype "passive"))
      (node (ref "C202") (pin "1") (pinfunction "1_1") (pintype "passive"))
      (node (ref "C223") (pin "1") (pinfunction "1_1") (pintype "passive"))
      (node (ref "C227") (pin "1") (pinfunction "1_1") (pintype "passive"))
      (node (ref "C285") (pin "1") (pinfunction "1_1") (pintype "passive"))
      (node (ref "C302") (pin "1") (pinfunction "1_1") (pintype "passive"))
      (node (ref "R141") (pin "2") (pinfunction "2_2") (pintype "passive"))
      (node (ref "R145") (pin "2") (pinfunction "2_2") (pintype "passive"))
      (node (ref "U22") (pin "R10") (pinfunction "VDDSOC_CAP_1_R10") (pintype "passive"))
      (node (ref "U22") (pin "T10") (pinfunction "VDDSOC_CAP_2_T10") (pintype "passive"))
      (node (ref "U22") (pin "T13") (pinfunction "VDDSOC_CAP_3_T13") (pintype "passive"))
      (node (ref "U22") (pin "T14") (pinfunction "VDDSOC_CAP_4_T14") (pintype "passive"))
      (node (ref "U22") (pin "U10") (pinfunction "VDDSOC_CAP_5_U10") (pintype "passive"))
      (node (ref "U22") (pin "U13") (pinfunction "VDDSOC_CAP_6_U13") (pintype "passive"))
      (node (ref "U22") (pin "U14") (pinfunction "VDDSOC_CAP_7_U14") (pintype "passive"))
    )
    (net (code "24") (name "VDD_SOC_IN") (class "Default")
      (node (ref "C116") (pin "1") (pinfunction "1_1") (pintype "passive"))
      (node (ref "C229") (pin "1") (pinfunction "1_1") (pintype "passive"))
      (node (ref "C282") (pin "1") (pinfunction "1_1") (pintype "passive"))
      (node (ref "C283") (pin "1") (pinfunction "1_1") (pintype "passive"))
      (node (ref "U22") (pin "H16") (pinfunction "VDDSOC_IN_1_H16") (pintype "passive"))
      (node (ref "U22") (pin "J16") (pinfunction "VDDSOC_IN_2_J16") (pintype "passive"))
      (node (ref "U22") (pin "K16") (pinfunction "VDDSOC_IN_3_K16") (pintype "passive"))
      (node (ref "U22") (pin "L16") (pinfunction "VDDSOC_IN_4_L16") (pintype "passive"))
      (node (ref "U22") (pin "M16") (pinfunction "VDDSOC_IN_5_M16") (pintype "passive"))
      (node (ref "U22") (pin "N16") (pinfunction "VDDSOC_IN_6_N16") (pintype "passive"))
      (node (ref "U22") (pin "P16") (pinfunction "VDDSOC_IN_7_P16") (pintype "passive"))
      (node (ref "U22") (pin "R16") (pinfunction "VDDSOC_IN_8_R16") (pintype "passive"))
      (node (ref "U22") (pin "T16") (pinfunction "VDDSOC_IN_9_T16") (pintype "passive"))
      (node (ref "U22") (pin "U16") (pinfunction "VDDSOC_IN_10_U16") (pintype "passive"))
    )
    (net (code "25") (name "VDD_SRTC_MX") (class "Default")
      (node (ref "R583") (pin "1") (pinfunction "1_1") (pintype "passive"))
    )
    (net (code "26") (name "VDD_VP") (class "Default")
      (node (ref "C287") (pin "1") (pinfunction "1_1") (pintype "passive"))
      (node (ref "C88") (pin "1") (pinfunction "1_1") (pintype "passive"))
      (node (ref "C89") (pin "1") (pinfunction "1_1") (pintype "passive"))
      (node (ref "C96") (pin "1") (pinfunction "1_1") (pintype "passive"))
      (node (ref "R145") (pin "1") (pinfunction "1_1") (pintype "passive"))
      (node (ref "U22") (pin "G13") (pinfunction "SATA_VP_G13") (pintype "passive"))
      (node (ref "U22") (pin "G8") (pinfunction "PCIE_VPTX_G8") (pintype "passive"))
      (node (ref "U22") (pin "H7") (pinfunction "PCIE_VP_H7") (pintype "passive"))
      (node (ref "U22") (pin "L7") (pinfunction "HDMI_VP_L7") (pintype "passive"))
    )
    (net (code "27") (name "VDD_VPH") (class "Default")
      (node (ref "C108") (pin "1") (pinfunction "1_1") (pintype "passive"))
      (node (ref "C109") (pin "1") (pinfunction "1_1") (pintype "passive"))
      (node (ref "C232") (pin "1") (pinfunction "1_1") (pintype "passive"))
      (node (ref "C99") (pin "1") (pinfunction "1_1") (pintype "passive"))
      (node (ref "R144") (pin "1") (pinfunction "1_1") (pintype "passive"))
      (node (ref "U22") (pin "G12") (pinfunction "SATA_VPH_G12") (pintype "passive"))
      (node (ref "U22") (pin "G7") (pinfunction "PCIE_VPH_G7") (pintype "passive"))
      (node (ref "U22") (pin "M7") (pinfunction "HDMI_VPH_M7") (pintype "passive"))
    )
    (net (code "28") (name "VDD_VPU") (class "Default")
      (node (ref "C11") (pin "1") (pinfunction "1_1") (pintype "passive"))
      (node (ref "C150") (pin "1") (pinfunction "1_1") (pintype "passive"))
      (node (ref "C19") (pin "1") (pinfunction "1_1") (pintype "passive"))
      (node (ref "C260") (pin "1") (pinfunction "1_1") (pintype "passive"))
      (node (ref "C263") (pin "1") (pinfunction "1_1") (pintype "passive"))
      (node (ref "C304") (pin "1") (pinfunction "1_1") (pintype "passive"))
      (node (ref "U22") (pin "H17") (pinfunction "VDDPU_CAP_1_H17") (pintype "passive"))
      (node (ref "U22") (pin "J17") (pinfunction "VDDPU_CAP_2_J17") (pintype "passive"))
      (node (ref "U22") (pin "K17") (pinfunction "VDDPU_CAP_3_K17") (pintype "passive"))
      (node (ref "U22") (pin "L17") (pinfunction "VDDPU_CAP_4_L17") (pintype "passive"))
      (node (ref "U22") (pin "M17") (pinfunction "VDDPU_CAP_5_M17") (pintype "passive"))
      (node (ref "U22") (pin "N17") (pinfunction "VDDPU_CAP_6_N17") (pintype "passive"))
      (node (ref "U22") (pin "P17") (pinfunction "VDDPU_CAP_7_P17") (pintype "passive"))
    )
    (net (code "29") (name "unconnected-(TP8-TP-Pad1)") (class "Default")
      (node (ref "TP8") (pin "1") (pinfunction "TP_1") (pintype "passive"))
    )
    (net (code "30") (name "unconnected-(TP9-TP-Pad1)") (class "Default")
      (node (ref "TP9") (pin "1") (pinfunction "TP_1") (pintype "passive"))
    )
    (net (code "31") (name "unconnected-(U22C-FA_ANA-PadA5)") (class "Default")
      (node (ref "U22") (pin "A5") (pinfunction "FA_ANA_A5") (pintype "passive"))
    )
    (net (code "32") (name "unconnected-(U22C-GPANAIO-PadC8)") (class "Default")
      (node (ref "U22") (pin "C8") (pinfunction "GPANAIO_C8") (pintype "passive"))
    )
    (net (code "33") (name "unconnected-(U22C-VDD_FA-PadB5)") (class "Default")
      (node (ref "U22") (pin "B5") (pinfunction "VDD_FA_B5") (pintype "passive"))
    )
  )
)
